# BM71BreakoutSchematic.net
KiCad netlist of a schematic drawn in Altium Designer
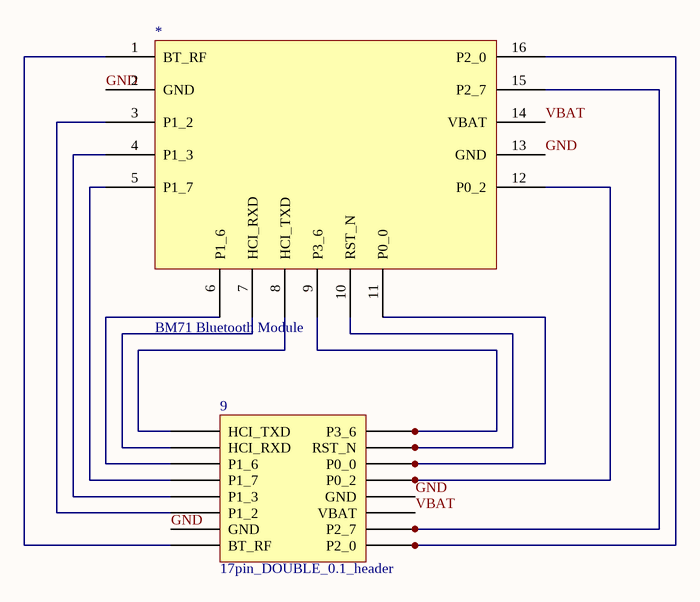
[diagram p0: BM71BreakoutSchematic.SchDoc]

(export (version "E")
  (design (tool "Eeschema 10.0.6"))
  (components
    (comp (ref "*")
      (value "BM71 Bluetooth Module")
      (footprint "BM71BLES1FC2")
      (libsource (lib "BM71BLES1FC2") (part "BM71 Bluetooth Module"))
    )
    (comp (ref "9")
      (value "17pin_DOUBLE_0.1_header")
      (footprint "17pin_DOUBLE_0.1_header")
      (libsource (lib "ArduinoHeader") (part "17pin_DOUBLE_0.1_header"))
    )
  )
  (nets
    (net (code "1") (name "/GND") (class "Default")
      (node (ref "*") (pin "13") (pinfunction "GND_13") (pintype "passive"))
      (node (ref "*") (pin "2") (pinfunction "GND_2") (pintype "passive"))
      (node (ref "9") (pin "13") (pinfunction "GND_13") (pintype "passive"))
      (node (ref "9") (pin "2") (pinfunction "GND_2") (pintype "passive"))
    )
    (net (code "2") (name "/VBAT") (class "Default")
      (node (ref "*") (pin "14") (pinfunction "VBAT_14") (pintype "passive"))
      (node (ref "9") (pin "14") (pinfunction "VBAT_14") (pintype "passive"))
    )
    (net (code "3") (name "Net-(*-BT_RF)") (class "Default")
      (node (ref "*") (pin "1") (pinfunction "BT_RF_1") (pintype "passive"))
      (node (ref "9") (pin "1") (pinfunction "BT_RF_1") (pintype "passive"))
    )
    (net (code "4") (name "Net-(*-HCI_RXD)") (class "Default")
      (node (ref "*") (pin "7") (pinfunction "HCI_RXD_7") (pintype "passive"))
      (node (ref "9") (pin "7") (pinfunction "HCI_RXD_7") (pintype "passive"))
    )
    (net (code "5") (name "Net-(*-HCI_TXD)") (class "Default")
      (node (ref "*") (pin "8") (pinfunction "HCI_TXD_8") (pintype "passive"))
      (node (ref "9") (pin "8") (pinfunction "HCI_TXD_8") (pintype "passive"))
    )
    (net (code "6") (name "Net-(*-P0_0)") (class "Default")
      (node (ref "*") (pin "11") (pinfunction "P0_0_11") (pintype "passive"))
      (node (ref "9") (pin "11") (pinfunction "P0_0_11") (pintype "passive"))
    )
    (net (code "7") (name "Net-(*-P0_2)") (class "Default")
      (node (ref "*") (pin "12") (pinfunction "P0_2_12") (pintype "passive"))
      (node (ref "9") (pin "12") (pinfunction "P0_2_12") (pintype "passive"))
    )
    (net (code "8") (name "Net-(*-P1_2)") (class "Default")
      (node (ref "*") (pin "3") (pinfunction "P1_2_3") (pintype "passive"))
      (node (ref "9") (pin "3") (pinfunction "P1_2_3") (pintype "passive"))
    )
    (net (code "9") (name "Net-(*-P1_3)") (class "Default")
      (node (ref "*") (pin "4") (pinfunction "P1_3_4") (pintype "passive"))
      (node (ref "9") (pin "4") (pinfunction "P1_3_4") (pintype "passive"))
    )
    (net (code "10") (name "Net-(*-P1_6)") (class "Default")
      (node (ref "*") (pin "6") (pinfunction "P1_6_6") (pintype "passive"))
      (node (ref "9") (pin "6") (pinfunction "P1_6_6") (pintype "passive"))
    )
    (net (code "11") (name "Net-(*-P1_7)") (class "Default")
      (node (ref "*") (pin "5") (pinfunction "P1_7_5") (pintype "passive"))
      (node (ref "9") (pin "5") (pinfunction "P1_7_5") (pintype "passive"))
    )
    (net (code "12") (name "Net-(*-P2_0)") (class "Default")
      (node (ref "*") (pin "16") (pinfunction "P2_0_16") (pintype "passive"))
      (node (ref "9") (pin "16") (pinfunction "P2_0_16") (pintype "passive"))
    )
    (net (code "13") (name "Net-(*-P2_7)") (class "Default")
      (node (ref "*") (pin "15") (pinfunction "P2_7_15") (pintype "passive"))
      (node (ref "9") (pin "15") (pinfunction "P2_7_15") (pintype "passive"))
    )
    (net (code "14") (name "Net-(*-P3_6)") (class "Default")
      (node (ref "*") (pin "9") (pinfunction "P3_6_9") (pintype "passive"))
      (node (ref "9") (pin "9") (pinfunction "P3_6_9") (pintype "passive"))
    )
    (net (code "15") (name "Net-(*-RST_N)") (class "Default")
      (node (ref "*") (pin "10") (pinfunction "RST_N_10") (pintype "passive"))
      (node (ref "9") (pin "10") (pinfunction "RST_N_10") (pintype "passive"))
    )
  )
)
